# quad-ultimax-cartridge.net
KiCad netlist of a schematic drawn in EAGLE
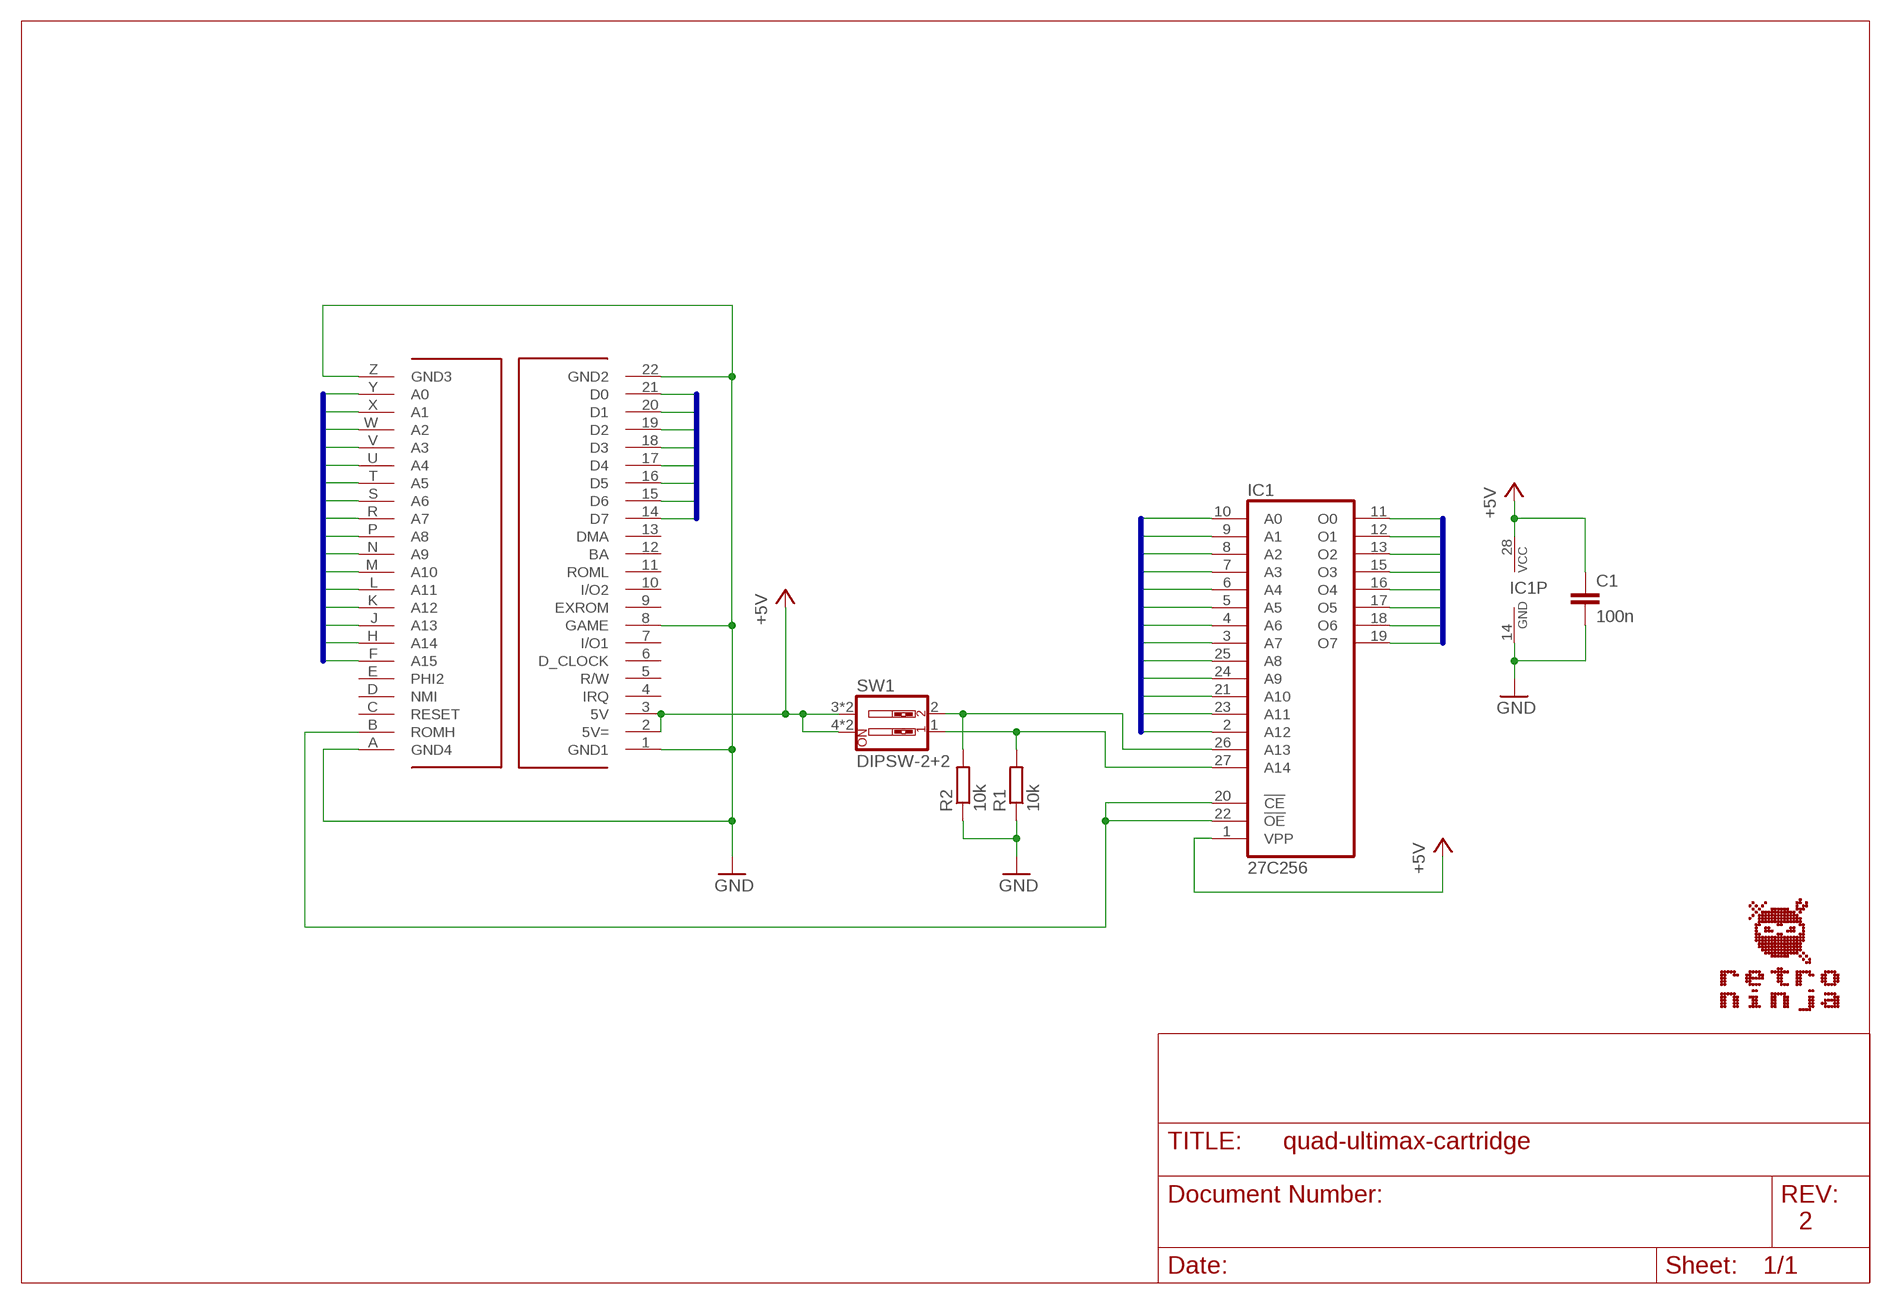
[diagram p0: schematic, sheet 1]

(export (version "E")
  (design (tool "Eeschema 10.0.6"))
  (components
    (comp (ref "C1")
      (value "100n")
      (footprint "eagle-import:CAP_5MM_2.5X5.0_ROUND")
      (libsource (lib "eagle-import") (part "CAPACITOR"))
    )
    (comp (ref "IC1")
      (value "27C256")
      (footprint "eagle-import:DIL28")
      (libsource (lib "eagle-import") (part "27256"))
    )
    (comp (ref "R1")
      (value "10k")
      (footprint "eagle-import:0207_10")
      (libsource (lib "eagle-import") (part "RESISTOR10MM"))
    )
    (comp (ref "R2")
      (value "10k")
      (footprint "eagle-import:0207_10")
      (libsource (lib "eagle-import") (part "RESISTOR10MM"))
    )
    (comp (ref "SW1")
      (value "DIPSW-2+2")
      (footprint "eagle-import:DIPSW2+2")
      (libsource (lib "eagle-import") (part "DIPSW-2+2"))
    )
    (comp (ref "U$1")
      (value "C64CARTRIDGE_BOARD_CONNECTOR")
      (footprint "eagle-import:C64_CARTRIDGE_BOARDEDGE")
      (libsource (lib "eagle-import") (part "C64CARTRIDGE_BOARD_CONNECTOR"))
    )
  )
  (nets
    (net (code "1") (name "+5V") (class "Default")
      (node (ref "C1") (pin "1") (pinfunction "1_1") (pintype "passive"))
      (node (ref "IC1") (pin "1") (pinfunction "VPP_1") (pintype "input"))
      (node (ref "IC1") (pin "28") (pinfunction "VCC_28") (pintype "power_in"))
      (node (ref "SW1") (pin "3") (pinfunction "3_3") (pintype "passive"))
      (node (ref "SW1") (pin "4") (pinfunction "4_4") (pintype "passive"))
      (node (ref "SW1") (pin "5") (pinfunction "3_5") (pintype "passive"))
      (node (ref "SW1") (pin "6") (pinfunction "4_6") (pintype "passive"))
      (node (ref "U$1") (pin "2") (pinfunction "5V=_2") (pintype "bidirectional"))
      (node (ref "U$1") (pin "3") (pinfunction "5V_3") (pintype "bidirectional"))
    )
    (net (code "2") (name "/A0") (class "Default")
      (node (ref "IC1") (pin "10") (pinfunction "A0_10") (pintype "input"))
      (node (ref "U$1") (pin "Y") (pinfunction "A0_Y") (pintype "bidirectional"))
    )
    (net (code "3") (name "/A1") (class "Default")
      (node (ref "IC1") (pin "9") (pinfunction "A1_9") (pintype "input"))
      (node (ref "U$1") (pin "X") (pinfunction "A1_X") (pintype "bidirectional"))
    )
    (net (code "4") (name "/A2") (class "Default")
      (node (ref "IC1") (pin "8") (pinfunction "A2_8") (pintype "input"))
      (node (ref "U$1") (pin "W") (pinfunction "A2_W") (pintype "bidirectional"))
    )
    (net (code "5") (name "/A3") (class "Default")
      (node (ref "IC1") (pin "7") (pinfunction "A3_7") (pintype "input"))
      (node (ref "U$1") (pin "V") (pinfunction "A3_V") (pintype "bidirectional"))
    )
    (net (code "6") (name "/A4") (class "Default")
      (node (ref "IC1") (pin "6") (pinfunction "A4_6") (pintype "input"))
      (node (ref "U$1") (pin "U") (pinfunction "A4_U") (pintype "bidirectional"))
    )
    (net (code "7") (name "/A5") (class "Default")
      (node (ref "IC1") (pin "5") (pinfunction "A5_5") (pintype "input"))
      (node (ref "U$1") (pin "T") (pinfunction "A5_T") (pintype "bidirectional"))
    )
    (net (code "8") (name "/A6") (class "Default")
      (node (ref "IC1") (pin "4") (pinfunction "A6_4") (pintype "input"))
      (node (ref "U$1") (pin "S") (pinfunction "A6_S") (pintype "bidirectional"))
    )
    (net (code "9") (name "/A7") (class "Default")
      (node (ref "IC1") (pin "3") (pinfunction "A7_3") (pintype "input"))
      (node (ref "U$1") (pin "R") (pinfunction "A7_R") (pintype "bidirectional"))
    )
    (net (code "10") (name "/A8") (class "Default")
      (node (ref "IC1") (pin "25") (pinfunction "A8_25") (pintype "input"))
      (node (ref "U$1") (pin "P") (pinfunction "A8_P") (pintype "bidirectional"))
    )
    (net (code "11") (name "/A9") (class "Default")
      (node (ref "IC1") (pin "24") (pinfunction "A9_24") (pintype "input"))
      (node (ref "U$1") (pin "N") (pinfunction "A9_N") (pintype "bidirectional"))
    )
    (net (code "12") (name "/A10") (class "Default")
      (node (ref "IC1") (pin "21") (pinfunction "A10_21") (pintype "input"))
      (node (ref "U$1") (pin "M") (pinfunction "A10_M") (pintype "bidirectional"))
    )
    (net (code "13") (name "/A11") (class "Default")
      (node (ref "IC1") (pin "23") (pinfunction "A11_23") (pintype "input"))
      (node (ref "U$1") (pin "L") (pinfunction "A11_L") (pintype "bidirectional"))
    )
    (net (code "14") (name "/A12") (class "Default")
      (node (ref "IC1") (pin "2") (pinfunction "A12_2") (pintype "input"))
      (node (ref "U$1") (pin "K") (pinfunction "A12_K") (pintype "bidirectional"))
    )
    (net (code "15") (name "/D0") (class "Default")
      (node (ref "IC1") (pin "11") (pinfunction "O0_11") (pintype "tri_state"))
      (node (ref "U$1") (pin "21") (pinfunction "D0_21") (pintype "bidirectional"))
    )
    (net (code "16") (name "/D1") (class "Default")
      (node (ref "IC1") (pin "12") (pinfunction "O1_12") (pintype "tri_state"))
      (node (ref "U$1") (pin "20") (pinfunction "D1_20") (pintype "bidirectional"))
    )
    (net (code "17") (name "/D2") (class "Default")
      (node (ref "IC1") (pin "13") (pinfunction "O2_13") (pintype "tri_state"))
      (node (ref "U$1") (pin "19") (pinfunction "D2_19") (pintype "bidirectional"))
    )
    (net (code "18") (name "/D3") (class "Default")
      (node (ref "IC1") (pin "15") (pinfunction "O3_15") (pintype "tri_state"))
      (node (ref "U$1") (pin "18") (pinfunction "D3_18") (pintype "bidirectional"))
    )
    (net (code "19") (name "/D4") (class "Default")
      (node (ref "IC1") (pin "16") (pinfunction "O4_16") (pintype "tri_state"))
      (node (ref "U$1") (pin "17") (pinfunction "D4_17") (pintype "bidirectional"))
    )
    (net (code "20") (name "/D5") (class "Default")
      (node (ref "IC1") (pin "17") (pinfunction "O5_17") (pintype "tri_state"))
      (node (ref "U$1") (pin "16") (pinfunction "D5_16") (pintype "bidirectional"))
    )
    (net (code "21") (name "/D6") (class "Default")
      (node (ref "IC1") (pin "18") (pinfunction "O6_18") (pintype "tri_state"))
      (node (ref "U$1") (pin "15") (pinfunction "D6_15") (pintype "bidirectional"))
    )
    (net (code "22") (name "/D7") (class "Default")
      (node (ref "IC1") (pin "19") (pinfunction "O7_19") (pintype "tri_state"))
      (node (ref "U$1") (pin "14") (pinfunction "D7_14") (pintype "bidirectional"))
    )
    (net (code "23") (name "GND") (class "Default")
      (node (ref "C1") (pin "2") (pinfunction "2_2") (pintype "passive"))
      (node (ref "IC1") (pin "14") (pinfunction "GND_14") (pintype "power_in"))
      (node (ref "R1") (pin "1") (pinfunction "1_1") (pintype "passive"))
      (node (ref "R2") (pin "1") (pinfunction "1_1") (pintype "passive"))
      (node (ref "U$1") (pin "1") (pinfunction "GND1_1") (pintype "bidirectional"))
      (node (ref "U$1") (pin "22") (pinfunction "GND2_22") (pintype "bidirectional"))
      (node (ref "U$1") (pin "8") (pinfunction "GAME_8") (pintype "bidirectional"))
      (node (ref "U$1") (pin "A") (pinfunction "GND4_A") (pintype "bidirectional"))
      (node (ref "U$1") (pin "Z") (pinfunction "GND3_Z") (pintype "bidirectional"))
    )
    (net (code "24") (name "Net-(IC1A-A13)") (class "Default")
      (node (ref "IC1") (pin "26") (pinfunction "A13_26") (pintype "input"))
      (node (ref "R2") (pin "2") (pinfunction "2_2") (pintype "passive"))
      (node (ref "SW1") (pin "2") (pinfunction "2_2") (pintype "passive"))
    )
    (net (code "25") (name "Net-(IC1A-A14)") (class "Default")
      (node (ref "IC1") (pin "27") (pinfunction "A14_27") (pintype "input"))
      (node (ref "R1") (pin "2") (pinfunction "2_2") (pintype "passive"))
      (node (ref "SW1") (pin "1") (pinfunction "1_1") (pintype "passive"))
    )
    (net (code "26") (name "Net-(IC1A-~{CE})") (class "Default")
      (node (ref "IC1") (pin "20") (pinfunction "~{CE}_20") (pintype "input"))
      (node (ref "IC1") (pin "22") (pinfunction "~{OE}_22") (pintype "input"))
      (node (ref "U$1") (pin "B") (pinfunction "ROMH_B") (pintype "bidirectional"))
    )
    (net (code "27") (name "unconnected-(U$1-A13-PadJ)") (class "Default")
      (node (ref "U$1") (pin "J") (pinfunction "A13_J") (pintype "bidirectional"))
    )
    (net (code "28") (name "unconnected-(U$1-A14-PadH)") (class "Default")
      (node (ref "U$1") (pin "H") (pinfunction "A14_H") (pintype "bidirectional"))
    )
    (net (code "29") (name "unconnected-(U$1-A15-PadF)") (class "Default")
      (node (ref "U$1") (pin "F") (pinfunction "A15_F") (pintype "bidirectional"))
    )
    (net (code "30") (name "unconnected-(U$1-BA-Pad12)") (class "Default")
      (node (ref "U$1") (pin "12") (pinfunction "BA_12") (pintype "bidirectional"))
    )
    (net (code "31") (name "unconnected-(U$1-DMA-Pad13)") (class "Default")
      (node (ref "U$1") (pin "13") (pinfunction "DMA_13") (pintype "bidirectional"))
    )
    (net (code "32") (name "unconnected-(U$1-D_CLOCK-Pad6)") (class "Default")
      (node (ref "U$1") (pin "6") (pinfunction "D_CLOCK_6") (pintype "bidirectional"))
    )
    (net (code "33") (name "unconnected-(U$1-EXROM-Pad9)") (class "Default")
      (node (ref "U$1") (pin "9") (pinfunction "EXROM_9") (pintype "bidirectional"))
    )
    (net (code "34") (name "unconnected-(U$1-IRQ-Pad4)") (class "Default")
      (node (ref "U$1") (pin "4") (pinfunction "IRQ_4") (pintype "bidirectional"))
    )
    (net (code "35") (name "unconnected-(U$1-I{slash}O1-Pad7)") (class "Default")
      (node (ref "U$1") (pin "7") (pinfunction "I/O1_7") (pintype "bidirectional"))
    )
    (net (code "36") (name "unconnected-(U$1-I{slash}O2-Pad10)") (class "Default")
      (node (ref "U$1") (pin "10") (pinfunction "I/O2_10") (pintype "bidirectional"))
    )
    (net (code "37") (name "unconnected-(U$1-NMI-PadD)") (class "Default")
      (node (ref "U$1") (pin "D") (pinfunction "NMI_D") (pintype "bidirectional"))
    )
    (net (code "38") (name "unconnected-(U$1-PHI2-PadE)") (class "Default")
      (node (ref "U$1") (pin "E") (pinfunction "PHI2_E") (pintype "bidirectional"))
    )
    (net (code "39") (name "unconnected-(U$1-RESET-PadC)") (class "Default")
      (node (ref "U$1") (pin "C") (pinfunction "RESET_C") (pintype "bidirectional"))
    )
    (net (code "40") (name "unconnected-(U$1-ROML-Pad11)") (class "Default")
      (node (ref "U$1") (pin "11") (pinfunction "ROML_11") (pintype "bidirectional"))
    )
    (net (code "41") (name "unconnected-(U$1-R{slash}W-Pad5)") (class "Default")
      (node (ref "U$1") (pin "5") (pinfunction "R/W_5") (pintype "bidirectional"))
    )
  )
)
